# Half-Bridge_Convertor_ir2161s.net
KiCad netlist of a schematic drawn in Altium Designer
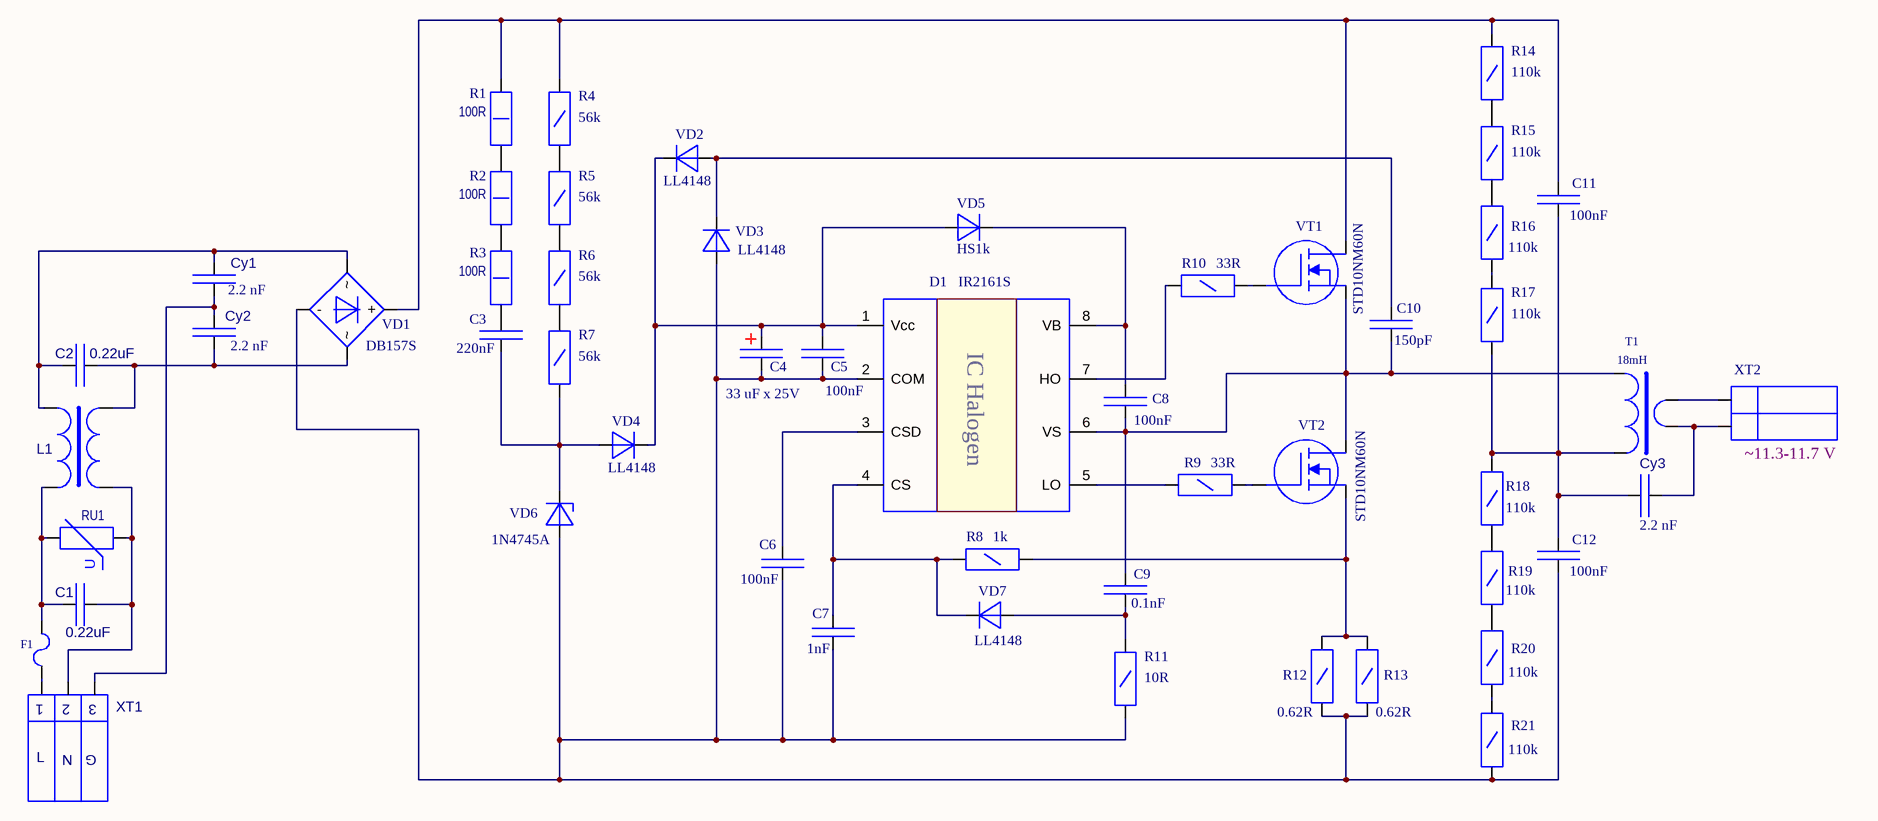
[diagram p0: Half-Bridge Convertor_ir2161s.SchDoc]

(export (version "E")
  (design (tool "Eeschema 10.0.6"))
  (components
    (comp (ref "C1")
      (value "0.22uF")
      (footprint "CAPR9.0x18.0-15.0")
      (description "Cap DIP (MKP)")
      (fields (field (name "VOLTAGE") "275VAC/400VDV") (field (name "TOLERANCE") "20%"))
      (libsource (lib "General Devices (laz)") (part "Cap_MKP"))
    )
    (comp (ref "C2")
      (value "0.22uF")
      (footprint "CAPR9.0x18.0-15.0")
      (description "Cap DIP (MKP)")
      (fields (field (name "VOLTAGE") "275VAC/400VDV") (field (name "TOLERANCE") "20%"))
      (libsource (lib "General Devices (laz)") (part "Cap_MKP"))
    )
    (comp (ref "C3")
      (value "220nF")
      (footprint "C2220")
      (description "Capacitor GOST")
      (fields (field (name "VOLTAGE") "630 V") (field (name "TOLERANCE") "10%"))
      (libsource (lib "General Devices (laz)") (part "Cap1"))
    )
    (comp (ref "C4")
      (value "33 uF x 25V")
      (footprint "CAPR5-4X5")
      (description "Cap Pol GOST")
      (fields (field (name "TOLERANCE") "10%") (field (name "Comment") "Cap Pol"))
      (libsource (lib "General Devices (laz)") (part "Cap Pol"))
    )
    (comp (ref "C5")
      (value "100nF")
      (footprint "CAPC2012 (0805)")
      (description "Capacitor GOST")
      (fields (field (name "VOLTAGE") "25 V") (field (name "TOLERANCE") "5%/10%"))
      (libsource (lib "General Devices (laz)") (part "Cap1"))
    )
    (comp (ref "C6")
      (value "100nF")
      (footprint "CAPC2012 (0805)")
      (description "Capacitor GOST")
      (fields (field (name "VOLTAGE") "25 V") (field (name "TOLERANCE") "5%/10%"))
      (libsource (lib "General Devices (laz)") (part "Cap1"))
    )
    (comp (ref "C7")
      (value "1nF")
      (footprint "CAPC2012 (0805)")
      (description "Capacitor GOST")
      (fields (field (name "VOLTAGE") "25 V") (field (name "TOLERANCE") "5%/10%"))
      (libsource (lib "General Devices (laz)") (part "Cap1"))
    )
    (comp (ref "C8")
      (value "100nF")
      (footprint "CAPC3216N")
      (description "Capacitor GOST")
      (fields (field (name "VOLTAGE") "50 V") (field (name "TOLERANCE") "5%/10%"))
      (libsource (lib "General Devices (laz)") (part "Cap1"))
    )
    (comp (ref "C9")
      (value "0.1nF")
      (footprint "CAPC2012 (0805)")
      (description "Capacitor GOST")
      (fields (field (name "VOLTAGE") "50 V") (field (name "TOLERANCE") "5%/10%"))
      (libsource (lib "General Devices (laz)") (part "Cap1"))
    )
    (comp (ref "C10")
      (value "150pF")
      (footprint "CAPR5.0x13.0-5.0")
      (description "Capacitor GOST")
      (fields (field (name "VOLTAGE") "1kV") (field (name "TOLERANCE") "10 %"))
      (libsource (lib "General Devices (laz)") (part "Cap1"))
    )
    (comp (ref "C11")
      (value "100nF")
      (footprint "CAPR9.0x18.0-15.0")
      (description "Capacitor GOST")
      (fields (field (name "VOLTAGE") "630V") (field (name "Comment") "Cap1"))
      (libsource (lib "General Devices (laz)") (part "Cap1"))
    )
    (comp (ref "C12")
      (value "100nF")
      (footprint "CAPR9.0x18.0-15.0")
      (description "Capacitor GOST")
      (fields (field (name "VOLTAGE") "630V") (field (name "Comment") "Cap1"))
      (libsource (lib "General Devices (laz)") (part "Cap1"))
    )
    (comp (ref "Cy1")
      (value "2.2 nF")
      (footprint "CAPR Y - 7.5")
      (description "Capacitor GOST")
      (fields (field (name "VOLTAGE") "275 VAC") (field (name "PART NUMBER") "MKY22W12203D00"))
      (libsource (lib "") (part "Cap1_1"))
    )
    (comp (ref "Cy2")
      (value "2.2 nF")
      (footprint "CAPR Y - 7.5")
      (description "Capacitor GOST")
      (fields (field (name "VOLTAGE") "275 VAC") (field (name "PART NUMBER") "MKY22W12203D00"))
      (libsource (lib "") (part "Cap1_1"))
    )
    (comp (ref "Cy3")
      (value "2.2 nF")
      (footprint "CAPR Y - 7.5")
      (description "Capacitor GOST")
      (fields (field (name "VOLTAGE") "275 VAC") (field (name "PART NUMBER") "MKY22W12203D00"))
      (libsource (lib "") (part "Cap1_1"))
    )
    (comp (ref "D1")
      (value "IR2161S")
      (footprint "SO8_M")
      (description "IC Halogen Converter")
      (libsource (lib "General Devices (laz)") (part "IR2161S"))
    )
    (comp (ref "F1")
      (value "Fuse3")
      (footprint "Fuse - PCB")
      (description "Fuse GOST")
      (libsource (lib "General Devices (laz)") (part "Fuse3"))
    )
    (comp (ref "L1")
      (value "Trans EMI")
      (footprint "YEE19-353D")
      (description "Trans EMI (GOST)")
      (libsource (lib "General Devices (laz)") (part "Trans EMI"))
    )
    (comp (ref "R1")
      (value "100R")
      (footprint "RESC6332")
      (description "Resistor GOST")
      (fields (field (name "TOLERANCE") "5%") (field (name "Comment") "Res 1W_1"))
      (libsource (lib "General Devices (laz)") (part "Res 1W_1"))
    )
    (comp (ref "R2")
      (value "100R")
      (footprint "RESC6332")
      (description "Resistor GOST")
      (fields (field (name "TOLERANCE") "5%") (field (name "Comment") "Res 1W_1"))
      (libsource (lib "General Devices (laz)") (part "Res 1W_1"))
    )
    (comp (ref "R3")
      (value "100R")
      (footprint "RESC6332")
      (description "Resistor GOST")
      (fields (field (name "TOLERANCE") "5%") (field (name "Comment") "Res 1W_1"))
      (libsource (lib "General Devices (laz)") (part "Res 1W_1"))
    )
    (comp (ref "R4")
      (value "56k")
      (footprint "RESC3216(1206)N")
      (description "Resistor GOST")
      (fields (field (name "TOLERANCE") "5%") (field (name "Comment") "Res 1/4W"))
      (libsource (lib "General Devices (laz)") (part "Res 1/4W"))
    )
    (comp (ref "R5")
      (value "56k")
      (footprint "RESC3216(1206)N")
      (description "Resistor GOST")
      (fields (field (name "TOLERANCE") "5%") (field (name "Comment") "Res 1/4W"))
      (libsource (lib "General Devices (laz)") (part "Res 1/4W"))
    )
    (comp (ref "R6")
      (value "56k")
      (footprint "RESC3216(1206)N")
      (description "Resistor GOST")
      (fields (field (name "TOLERANCE") "5%") (field (name "Comment") "Res 1/4W"))
      (libsource (lib "General Devices (laz)") (part "Res 1/4W"))
    )
    (comp (ref "R7")
      (value "56k")
      (footprint "RESC3216(1206)N")
      (description "Resistor GOST")
      (fields (field (name "TOLERANCE") "5%") (field (name "Comment") "Res 1/4W"))
      (libsource (lib "General Devices (laz)") (part "Res 1/4W"))
    )
    (comp (ref "R8")
      (value "1k")
      (footprint "RESC3216(1206)N")
      (description "Resistor GOST")
      (fields (field (name "TOLERANCE") "5%") (field (name "Comment") "Res 1/4W"))
      (libsource (lib "") (part "Res 1/4W_1"))
    )
    (comp (ref "R9")
      (value "33R")
      (footprint "RESC3216(1206)N")
      (description "Resistor GOST")
      (fields (field (name "Comment") "Res 1/8W"))
      (libsource (lib "") (part "Res 1/4W_1"))
    )
    (comp (ref "R10")
      (value "33R")
      (footprint "RESC3216(1206)N")
      (description "Resistor GOST")
      (fields (field (name "Comment") "Res 1/8W"))
      (libsource (lib "") (part "Res 1/4W_1"))
    )
    (comp (ref "R11")
      (value "10R")
      (footprint "RESC3216(1206)N")
      (description "Resistor GOST")
      (fields (field (name "TOLERANCE") "5%") (field (name "Comment") "Res 1/4W"))
      (libsource (lib "General Devices (laz)") (part "Res 1/4W"))
    )
    (comp (ref "R12")
      (value "0.62R")
      (footprint "RESC3216(1206)N")
      (description "Resistor GOST")
      (fields (field (name "TOLERANCE") "5%") (field (name "Comment") "Res 1/4W"))
      (libsource (lib "General Devices (laz)") (part "Res 1/4W"))
    )
    (comp (ref "R13")
      (value "0.62R")
      (footprint "RESC3216(1206)N")
      (description "Resistor GOST")
      (fields (field (name "TOLERANCE") "5%") (field (name "Comment") "Res 1/4W"))
      (libsource (lib "General Devices (laz)") (part "Res 1/4W"))
    )
    (comp (ref "R14")
      (value "110k")
      (footprint "RESC3216(1206)N")
      (description "Resistor GOST")
      (fields (field (name "TOLERANCE") "5%") (field (name "Comment") "Res 1/4W"))
      (libsource (lib "General Devices (laz)") (part "Res 1/4W"))
    )
    (comp (ref "R15")
      (value "110k")
      (footprint "RESC3216(1206)N")
      (description "Resistor GOST")
      (fields (field (name "TOLERANCE") "5%") (field (name "Comment") "Res 1/4W"))
      (libsource (lib "General Devices (laz)") (part "Res 1/4W"))
    )
    (comp (ref "R16")
      (value "110k")
      (footprint "RESC3216(1206)N")
      (description "Resistor GOST")
      (fields (field (name "TOLERANCE") "5%") (field (name "Comment") "Res 1/4W"))
      (libsource (lib "General Devices (laz)") (part "Res 1/4W"))
    )
    (comp (ref "R17")
      (value "110k")
      (footprint "RESC3216(1206)N")
      (description "Resistor GOST")
      (fields (field (name "TOLERANCE") "5%") (field (name "Comment") "Res 1/4W"))
      (libsource (lib "General Devices (laz)") (part "Res 1/4W"))
    )
    (comp (ref "R18")
      (value "110k")
      (footprint "RESC3216(1206)N")
      (description "Resistor GOST")
      (fields (field (name "TOLERANCE") "5%") (field (name "Comment") "Res 1/4W"))
      (libsource (lib "") (part "Res 1/4W_2"))
    )
    (comp (ref "R19")
      (value "110k")
      (footprint "RESC3216(1206)N")
      (description "Resistor GOST")
      (fields (field (name "TOLERANCE") "5%") (field (name "Comment") "Res 1/4W"))
      (libsource (lib "General Devices (laz)") (part "Res 1/4W"))
    )
    (comp (ref "R20")
      (value "110k")
      (footprint "RESC3216(1206)N")
      (description "Resistor GOST")
      (fields (field (name "TOLERANCE") "5%") (field (name "Comment") "Res 1/4W"))
      (libsource (lib "General Devices (laz)") (part "Res 1/4W"))
    )
    (comp (ref "R21")
      (value "110k")
      (footprint "RESC3216(1206)N")
      (description "Resistor GOST")
      (fields (field (name "TOLERANCE") "5%") (field (name "Comment") "Res 1/4W"))
      (libsource (lib "General Devices (laz)") (part "Res 1/4W"))
    )
    (comp (ref "RU1")
      (value "Varistor")
      (footprint "VAristor 7.5-11x5")
      (description "Varistor GOST")
      (fields (field (name "PART NUMBER") "ERZ-V05D471"))
      (libsource (lib "General Devices (laz)") (part "Varistor"))
    )
    (comp (ref "T1")
      (value "HLT-R29.5-18mH-0-g")
      (footprint "HLT-R29.5-18mH-0-g")
      (fields (field (name "VALUE2") "18mH"))
      (libsource (lib "General Devices (laz)") (part "Choke HLT- 50W/12V_1"))
    )
    (comp (ref "VD1")
      (value "DB157S")
      (footprint "DB-1S")
      (description "Diode Bridge GOST")
      (fields (field (name "Comment") "Diode Bridge"))
      (libsource (lib "General Devices (laz)") (part "Diode Bridge"))
    )
    (comp (ref "VD2")
      (value "LL4148")
      (footprint "MELF-D3516-1406")
      (description "Diode LL4148 (GOST)")
      (fields (field (name "Comment") "Diode LL4148"))
      (libsource (lib "General Devices (laz)") (part "Diode LL4148"))
    )
    (comp (ref "VD3")
      (value "LL4148")
      (footprint "MELF-D3516-1406")
      (description "Diode LL4148 (GOST)")
      (fields (field (name "Comment") "Diode LL4148"))
      (libsource (lib "General Devices (laz)") (part "Diode LL4148"))
    )
    (comp (ref "VD4")
      (value "LL4148")
      (footprint "MELF-D3516-1406")
      (description "Diode LL4148 (GOST)")
      (fields (field (name "Comment") "Diode LL4148"))
      (libsource (lib "General Devices (laz)") (part "Diode LL4148"))
    )
    (comp (ref "VD5")
      (value "HS1k")
      (footprint "CD4532-1812 (mod)")
      (description "Diode HS1x (GOST)")
      (fields (field (name "Comment") "Diode HS1x"))
      (libsource (lib "General Devices (laz)") (part "Diode HS1x"))
    )
    (comp (ref "VD6")
      (value "1N4745A")
      (footprint "DO-41")
      (description "Diode Zener GOST")
      (fields (field (name "Comment") "Diode Zener"))
      (libsource (lib "General Devices (laz)") (part "Diode Zener"))
    )
    (comp (ref "VD7")
      (value "LL4148")
      (footprint "MELF-D3516-1406")
      (description "Diode LL4148 (GOST)")
      (fields (field (name "Comment") "Diode LL4148"))
      (libsource (lib "General Devices (laz)") (part "Diode LL4148"))
    )
    (comp (ref "VT1")
      (value "STD10NM60N")
      (footprint "D-PAK (TO252)")
      (description "MOSFET N-channel (GOST)")
      (fields (field (name "Comment") "IRFBC40S"))
      (libsource (lib "General Devices (laz)") (part "FQD5N50"))
    )
    (comp (ref "VT2")
      (value "STD10NM60N")
      (footprint "D-PAK (TO252)")
      (description "MOSFET N-channel (GOST)")
      (fields (field (name "Comment") "IRFBC40S"))
      (libsource (lib "General Devices (laz)") (part "FQD5N50"))
    )
    (comp (ref "XT1")
      (value "Connect x3")
      (footprint "ZIP-Ballast3")
      (description "Connect x3 GOST")
      (libsource (lib "General Devices (laz)") (part "Connect x3"))
    )
    (comp (ref "XT2")
      (value "Connect x2")
      (footprint "ZIP-Ballast2x3")
      (description "Connect x2 GOST")
      (libsource (lib "General Devices (laz)") (part "Connect x2"))
    )
  )
  (nets
    (net (code "1") (name "Net-(C3-Pad1)") (class "Default")
      (node (ref "C3") (pin "1") (pinfunction "1_1") (pintype "passive"))
      (node (ref "R7") (pin "2") (pinfunction "2_2") (pintype "passive"))
      (node (ref "VD4") (pin "1") (pinfunction "1_1") (pintype "passive"))
      (node (ref "VD6") (pin "2") (pinfunction "2_2") (pintype "passive"))
    )
    (net (code "2") (name "Net-(C3-Pad2)") (class "Default")
      (node (ref "C3") (pin "2") (pinfunction "2_2") (pintype "passive"))
      (node (ref "R3") (pin "2") (pinfunction "2_2") (pintype "passive"))
    )
    (net (code "3") (name "Net-(C9-Pad1)") (class "Default")
      (node (ref "C9") (pin "1") (pinfunction "1_1") (pintype "passive"))
      (node (ref "R11") (pin "1") (pinfunction "1_1") (pintype "passive"))
      (node (ref "VD7") (pin "1") (pinfunction "1_1") (pintype "passive"))
    )
    (net (code "4") (name "Net-(C10-Pad1)") (class "Default")
      (node (ref "C10") (pin "1") (pinfunction "1_1") (pintype "passive"))
      (node (ref "VD2") (pin "1") (pinfunction "1_1") (pintype "passive"))
      (node (ref "VD3") (pin "2") (pinfunction "2_2") (pintype "passive"))
    )
    (net (code "5") (name "Net-(Cy1-Pad1)") (class "Default")
      (node (ref "Cy1") (pin "1") (pinfunction "1_1") (pintype "passive"))
      (node (ref "Cy2") (pin "2") (pinfunction "2_2") (pintype "passive"))
      (node (ref "XT1") (pin "3") (pinfunction "3_3") (pintype "passive"))
    )
    (net (code "6") (name "Net-(D1-COM)") (class "Default")
      (node (ref "C12") (pin "1") (pinfunction "1_1") (pintype "passive"))
      (node (ref "C4") (pin "2") (pinfunction "2_2") (pintype "passive"))
      (node (ref "C5") (pin "1") (pinfunction "1_1") (pintype "passive"))
      (node (ref "C6") (pin "1") (pinfunction "1_1") (pintype "passive"))
      (node (ref "C7") (pin "1") (pinfunction "1_1") (pintype "passive"))
      (node (ref "D1") (pin "2") (pinfunction "COM_2") (pintype "passive"))
      (node (ref "R11") (pin "2") (pinfunction "2_2") (pintype "passive"))
      (node (ref "R12") (pin "2") (pinfunction "2_2") (pintype "passive"))
      (node (ref "R13") (pin "2") (pinfunction "2_2") (pintype "passive"))
      (node (ref "R21") (pin "2") (pinfunction "2_2") (pintype "passive"))
      (node (ref "VD1") (pin "4") (pinfunction "-_4") (pintype "passive"))
      (node (ref "VD3") (pin "1") (pinfunction "1_1") (pintype "passive"))
      (node (ref "VD6") (pin "1") (pinfunction "1_1") (pintype "passive"))
    )
    (net (code "7") (name "Net-(D1-CS)") (class "Default")
      (node (ref "C7") (pin "2") (pinfunction "2_2") (pintype "passive"))
      (node (ref "D1") (pin "4") (pinfunction "CS_4") (pintype "passive"))
      (node (ref "R8") (pin "1") (pinfunction "1_1") (pintype "passive"))
      (node (ref "VD7") (pin "2") (pinfunction "2_2") (pintype "passive"))
    )
    (net (code "8") (name "Net-(D1-CSD)") (class "Default")
      (node (ref "C6") (pin "2") (pinfunction "2_2") (pintype "passive"))
      (node (ref "D1") (pin "3") (pinfunction "CSD_3") (pintype "passive"))
    )
    (net (code "9") (name "Net-(D1-HO)") (class "Default")
      (node (ref "D1") (pin "7") (pinfunction "HO_7") (pintype "passive"))
      (node (ref "R10") (pin "1") (pinfunction "1_1") (pintype "passive"))
    )
    (net (code "10") (name "Net-(D1-LO)") (class "Default")
      (node (ref "D1") (pin "5") (pinfunction "LO_5") (pintype "passive"))
      (node (ref "R9") (pin "1") (pinfunction "1_1") (pintype "passive"))
    )
    (net (code "11") (name "Net-(D1-VB)") (class "Default")
      (node (ref "C8") (pin "2") (pinfunction "2_2") (pintype "passive"))
      (node (ref "D1") (pin "8") (pinfunction "VB_8") (pintype "passive"))
      (node (ref "VD5") (pin "2") (pinfunction "2_2") (pintype "passive"))
    )
    (net (code "12") (name "Net-(D1-VS)") (class "Default")
      (node (ref "C10") (pin "2") (pinfunction "2_2") (pintype "passive"))
      (node (ref "C8") (pin "1") (pinfunction "1_1") (pintype "passive"))
      (node (ref "C9") (pin "2") (pinfunction "2_2") (pintype "passive"))
      (node (ref "D1") (pin "6") (pinfunction "VS_6") (pintype "passive"))
      (node (ref "T1") (pin "2") (pinfunction "Pri+_2") (pintype "passive"))
      (node (ref "VT1") (pin "3") (pinfunction "S_3") (pintype "passive"))
      (node (ref "VT2") (pin "2") (pinfunction "D_2") (pintype "passive"))
    )
    (net (code "13") (name "Net-(D1-Vcc)") (class "Default")
      (node (ref "C4") (pin "1") (pinfunction "1_1") (pintype "passive"))
      (node (ref "C5") (pin "2") (pinfunction "2_2") (pintype "passive"))
      (node (ref "D1") (pin "1") (pinfunction "Vcc_1") (pintype "passive"))
      (node (ref "VD2") (pin "2") (pinfunction "2_2") (pintype "passive"))
      (node (ref "VD4") (pin "2") (pinfunction "2_2") (pintype "passive"))
      (node (ref "VD5") (pin "1") (pinfunction "1_1") (pintype "passive"))
    )
    (net (code "14") (name "Net-(F1-2)") (class "Default")
      (node (ref "C1") (pin "2") (pinfunction "2_2") (pintype "passive"))
      (node (ref "F1") (pin "1") (pinfunction "2_1") (pintype "passive"))
      (node (ref "L1") (pin "3") (pinfunction "Pri-_3") (pintype "passive"))
      (node (ref "RU1") (pin "2") (pinfunction "2_2") (pintype "passive"))
    )
    (net (code "15") (name "Net-(F1-Pad1)") (class "Default")
      (node (ref "F1") (pin "1") (pinfunction "1_1") (pintype "passive"))
      (node (ref "XT1") (pin "1") (pinfunction "1_1") (pintype "passive"))
    )
    (net (code "16") (name "Net-(L1-Pri+)") (class "Default")
      (node (ref "C2") (pin "2") (pinfunction "2_2") (pintype "passive"))
      (node (ref "Cy1") (pin "2") (pinfunction "2_2") (pintype "passive"))
      (node (ref "L1") (pin "4") (pinfunction "Pri+_4") (pintype "passive"))
      (node (ref "VD1") (pin "1") (pinfunction "~_1") (pintype "passive"))
    )
    (net (code "17") (name "Net-(L1-Sec+)") (class "Default")
      (node (ref "C2") (pin "1") (pinfunction "1_1") (pintype "passive"))
      (node (ref "Cy2") (pin "1") (pinfunction "1_1") (pintype "passive"))
      (node (ref "L1") (pin "1") (pinfunction "Sec+_1") (pintype "passive"))
      (node (ref "VD1") (pin "2") (pinfunction "~_2") (pintype "passive"))
    )
    (net (code "18") (name "Net-(L1-Sec-)") (class "Default")
      (node (ref "C1") (pin "1") (pinfunction "1_1") (pintype "passive"))
      (node (ref "L1") (pin "2") (pinfunction "Sec-_2") (pintype "passive"))
      (node (ref "RU1") (pin "1") (pinfunction "1_1") (pintype "passive"))
      (node (ref "XT1") (pin "2") (pinfunction "2_2") (pintype "passive"))
    )
    (net (code "19") (name "Net-(R1-Pad2)") (class "Default")
      (node (ref "R1") (pin "2") (pinfunction "2_2") (pintype "passive"))
      (node (ref "R2") (pin "1") (pinfunction "1_1") (pintype "passive"))
    )
    (net (code "20") (name "Net-(R2-Pad2)") (class "Default")
      (node (ref "R2") (pin "2") (pinfunction "2_2") (pintype "passive"))
      (node (ref "R3") (pin "1") (pinfunction "1_1") (pintype "passive"))
    )
    (net (code "21") (name "Net-(R4-Pad2)") (class "Default")
      (node (ref "R4") (pin "2") (pinfunction "2_2") (pintype "passive"))
      (node (ref "R5") (pin "1") (pinfunction "1_1") (pintype "passive"))
    )
    (net (code "22") (name "Net-(R5-Pad2)") (class "Default")
      (node (ref "R5") (pin "2") (pinfunction "2_2") (pintype "passive"))
      (node (ref "R6") (pin "1") (pinfunction "1_1") (pintype "passive"))
    )
    (net (code "23") (name "Net-(R6-Pad2)") (class "Default")
      (node (ref "R6") (pin "2") (pinfunction "2_2") (pintype "passive"))
      (node (ref "R7") (pin "1") (pinfunction "1_1") (pintype "passive"))
    )
    (net (code "24") (name "Net-(R14-Pad2)") (class "Default")
      (node (ref "R14") (pin "2") (pinfunction "2_2") (pintype "passive"))
      (node (ref "R15") (pin "1") (pinfunction "1_1") (pintype "passive"))
    )
    (net (code "25") (name "Net-(R15-Pad2)") (class "Default")
      (node (ref "R15") (pin "2") (pinfunction "2_2") (pintype "passive"))
      (node (ref "R16") (pin "1") (pinfunction "1_1") (pintype "passive"))
    )
    (net (code "26") (name "Net-(R16-Pad2)") (class "Default")
      (node (ref "R16") (pin "2") (pinfunction "2_2") (pintype "passive"))
      (node (ref "R17") (pin "1") (pinfunction "1_1") (pintype "passive"))
    )
    (net (code "27") (name "Net-(R18-Pad1)") (class "Default")
      (node (ref "R18") (pin "1") (pinfunction "1_1") (pintype "passive"))
      (node (ref "R19") (pin "1") (pinfunction "1_1") (pintype "passive"))
    )
    (net (code "28") (name "Net-(R19-Pad2)") (class "Default")
      (node (ref "R19") (pin "2") (pinfunction "2_2") (pintype "passive"))
      (node (ref "R20") (pin "1") (pinfunction "1_1") (pintype "passive"))
    )
    (net (code "29") (name "Net-(R20-Pad2)") (class "Default")
      (node (ref "R20") (pin "2") (pinfunction "2_2") (pintype "passive"))
      (node (ref "R21") (pin "1") (pinfunction "1_1") (pintype "passive"))
    )
    (net (code "30") (name "Net-(T1-Pri-)") (class "Default")
      (node (ref "C11") (pin "1") (pinfunction "1_1") (pintype "passive"))
      (node (ref "C12") (pin "2") (pinfunction "2_2") (pintype "passive"))
      (node (ref "Cy3") (pin "2") (pinfunction "2_2") (pintype "passive"))
      (node (ref "R17") (pin "2") (pinfunction "2_2") (pintype "passive"))
      (node (ref "R18") (pin "2") (pinfunction "2_2") (pintype "passive"))
      (node (ref "T1") (pin "1") (pinfunction "Pri-_1") (pintype "passive"))
    )
    (net (code "31") (name "Net-(T1-Sec+)") (class "Default")
      (node (ref "T1") (pin "3") (pinfunction "Sec+_3") (pintype "passive"))
      (node (ref "XT2") (pin "2") (pinfunction "2_2") (pintype "passive"))
    )
    (net (code "32") (name "Net-(T1-Sec-)") (class "Default")
      (node (ref "Cy3") (pin "1") (pinfunction "1_1") (pintype "passive"))
      (node (ref "T1") (pin "4") (pinfunction "Sec-_4") (pintype "passive"))
      (node (ref "XT2") (pin "1") (pinfunction "1_1") (pintype "passive"))
    )
    (net (code "33") (name "Net-(VD1-+)") (class "Default")
      (node (ref "C11") (pin "2") (pinfunction "2_2") (pintype "passive"))
      (node (ref "R1") (pin "1") (pinfunction "1_1") (pintype "passive"))
      (node (ref "R14") (pin "1") (pinfunction "1_1") (pintype "passive"))
      (node (ref "R4") (pin "1") (pinfunction "1_1") (pintype "passive"))
      (node (ref "VD1") (pin "3") (pinfunction "+_3") (pintype "passive"))
      (node (ref "VT1") (pin "2") (pinfunction "D_2") (pintype "passive"))
    )
    (net (code "34") (name "Net-(VT1-G)") (class "Default")
      (node (ref "R10") (pin "2") (pinfunction "2_2") (pintype "passive"))
      (node (ref "VT1") (pin "1") (pinfunction "G_1") (pintype "passive"))
    )
    (net (code "35") (name "Net-(VT2-G)") (class "Default")
      (node (ref "R9") (pin "2") (pinfunction "2_2") (pintype "passive"))
      (node (ref "VT2") (pin "1") (pinfunction "G_1") (pintype "passive"))
    )
    (net (code "36") (name "Net-(VT2-S)") (class "Default")
      (node (ref "R12") (pin "1") (pinfunction "1_1") (pintype "passive"))
      (node (ref "R13") (pin "1") (pinfunction "1_1") (pintype "passive"))
      (node (ref "R8") (pin "2") (pinfunction "2_2") (pintype "passive"))
      (node (ref "VT2") (pin "3") (pinfunction "S_3") (pintype "passive"))
    )
  )
)
